# PMSM_500W_Controller_Bridge.net
KiCad netlist of a schematic drawn in Altium Designer
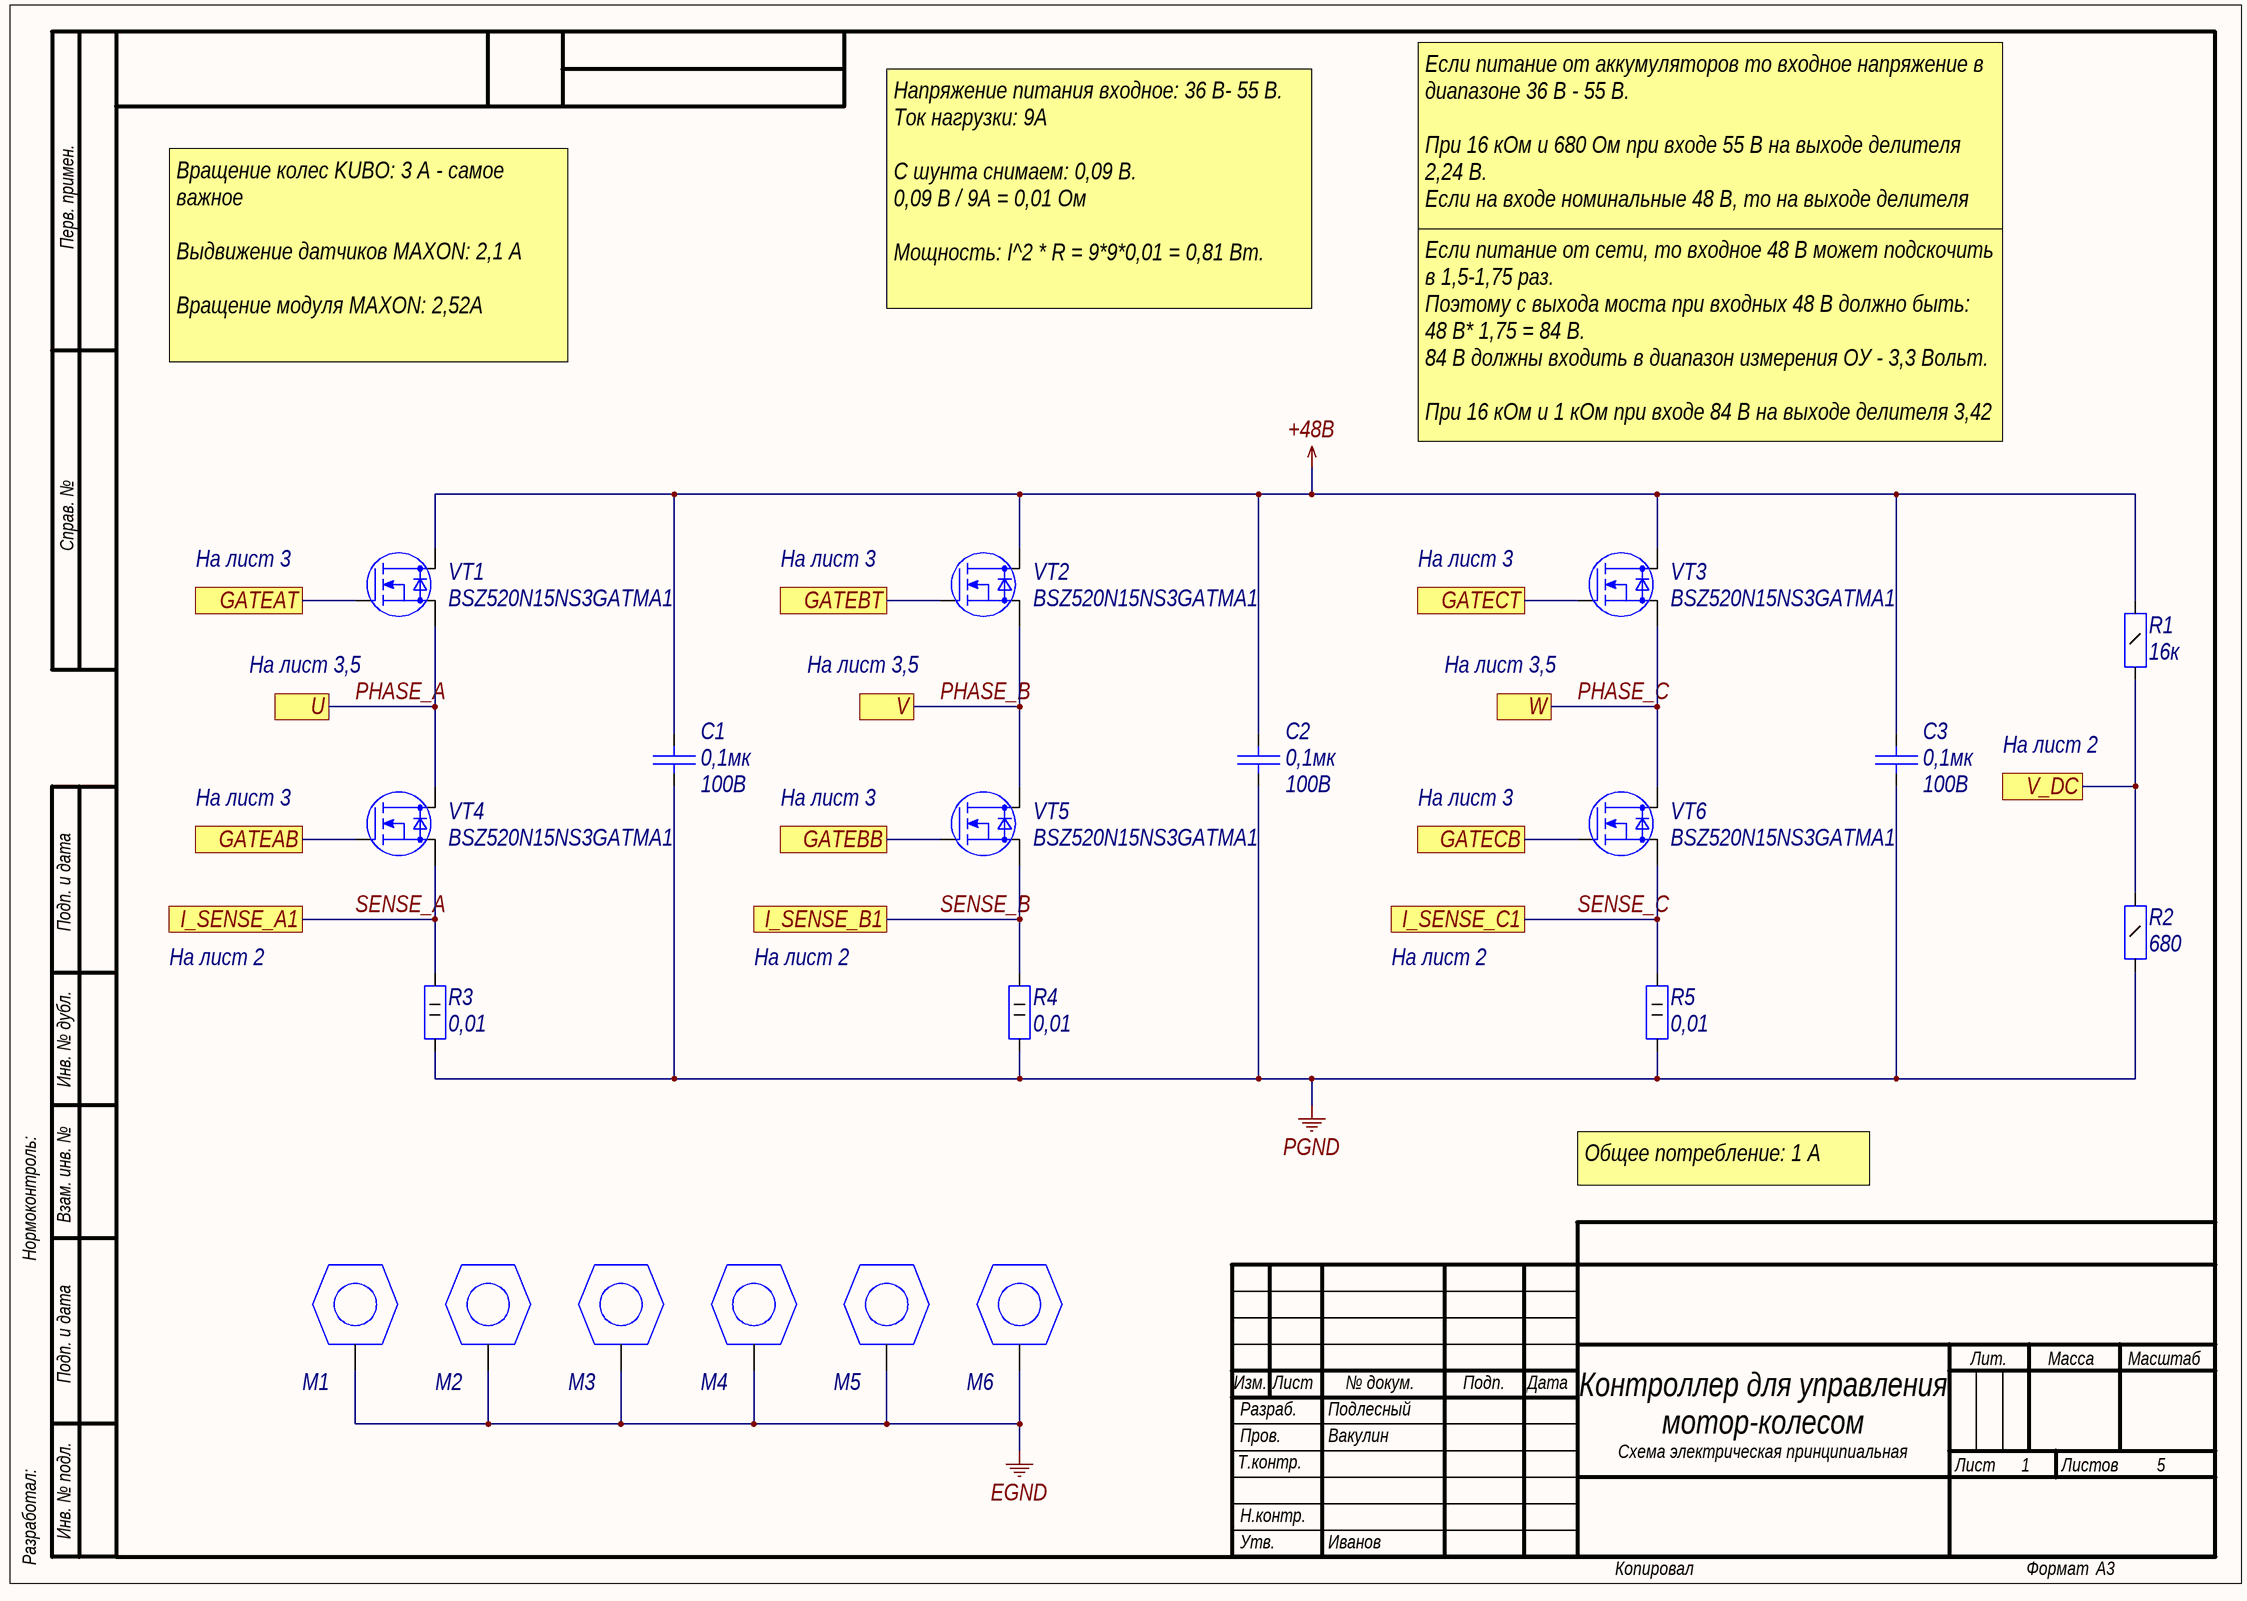
[diagram p0: PMSM_500W_Controller_Bridge.SchDoc]

(export (version "E")
  (design (tool "Eeschema 10.0.6"))
  (components
    (comp (ref "C1")
      (value "0,1мк")
      (footprint "C1206")
      (description "Конденсатор")
      (fields (field (name "VOLTAGE") "100В") (field (name "PART NUMBER") "GRM31C5C2A104JA01L"))
      (libsource (lib "MOP44") (part "Capacitor"))
    )
    (comp (ref "C2")
      (value "0,1мк")
      (footprint "C1206")
      (description "Конденсатор")
      (fields (field (name "VOLTAGE") "100В") (field (name "PART NUMBER") "GRM31C5C2A104JA01L"))
      (libsource (lib "MOP44") (part "Capacitor"))
    )
    (comp (ref "C3")
      (value "0,1мк")
      (footprint "C1206")
      (description "Конденсатор")
      (fields (field (name "VOLTAGE") "100В") (field (name "PART NUMBER") "GRM31C5C2A104JA01L"))
      (libsource (lib "MOP44") (part "Capacitor"))
    )
    (comp (ref "M1") (value "SCREW") (footprint "SCREW3") (libsource (lib "MOP44") (part "SCREW")))
    (comp (ref "M2") (value "SCREW") (footprint "SCREW3") (libsource (lib "MOP44") (part "SCREW")))
    (comp (ref "M3") (value "SCREW") (footprint "SCREW3") (libsource (lib "MOP44") (part "SCREW")))
    (comp (ref "M4") (value "SCREW") (footprint "SCREW3") (libsource (lib "MOP44") (part "SCREW")))
    (comp (ref "M5") (value "SCREW") (footprint "SCREW3") (libsource (lib "MOP44") (part "SCREW")))
    (comp (ref "M6") (value "SCREW") (footprint "SCREW3") (libsource (lib "MOP44") (part "SCREW")))
    (comp (ref "R1")
      (value "16к")
      (footprint "R1206")
      (description "Резистор")
      (fields (field (name "PART NUMBER") "RC1206FR-0716KL") (field (name "POWER") "0,25Вт"))
      (libsource (lib "MOP44") (part "Resistor_0,25Вт"))
    )
    (comp (ref "R2")
      (value "680")
      (footprint "R1206")
      (description "Резистор")
      (fields (field (name "PART NUMBER") "RC1206FR-07680RL") (field (name "POWER") "0,25Вт"))
      (libsource (lib "MOP44") (part "Resistor_0,25Вт"))
    )
    (comp (ref "R3")
      (value "0,01")
      (footprint "R2512")
      (description "Резистор")
      (fields (field (name "PART NUMBER") "CRA2512-FZ-R010ELF") (field (name "POWER") "2Вт"))
      (libsource (lib "MOP44") (part "Resistor_2Вт"))
    )
    (comp (ref "R4")
      (value "0,01")
      (footprint "R2512")
      (description "Резистор")
      (fields (field (name "PART NUMBER") "CRA2512-FZ-R010ELF") (field (name "POWER") "2Вт"))
      (libsource (lib "MOP44") (part "Resistor_2Вт"))
    )
    (comp (ref "R5")
      (value "0,01")
      (footprint "R2512")
      (description "Резистор")
      (fields (field (name "PART NUMBER") "CRA2512-FZ-R010ELF") (field (name "POWER") "2Вт"))
      (libsource (lib "MOP44") (part "Resistor_2Вт"))
    )
    (comp (ref "VT1")
      (value "N-MOSFET")
      (footprint "TSDSON8")
      (fields
        (field (name "PART NUMBER") "BSZ520N15NS3GATMA1")
        (field (name "MANUFACTURER") "Infineon Technologies")
      )
      (libsource (lib "MOP44") (part "N-MOSFET"))
    )
    (comp (ref "VT2")
      (value "N-MOSFET")
      (footprint "TSDSON8")
      (fields
        (field (name "PART NUMBER") "BSZ520N15NS3GATMA1")
        (field (name "MANUFACTURER") "Infineon Technologies")
      )
      (libsource (lib "MOP44") (part "N-MOSFET"))
    )
    (comp (ref "VT3")
      (value "N-MOSFET")
      (footprint "TSDSON8")
      (fields
        (field (name "PART NUMBER") "BSZ520N15NS3GATMA1")
        (field (name "MANUFACTURER") "Infineon Technologies")
      )
      (libsource (lib "MOP44") (part "N-MOSFET"))
    )
    (comp (ref "VT4")
      (value "N-MOSFET")
      (footprint "TSDSON8")
      (fields
        (field (name "PART NUMBER") "BSZ520N15NS3GATMA1")
        (field (name "MANUFACTURER") "Infineon Technologies")
      )
      (libsource (lib "MOP44") (part "N-MOSFET"))
    )
    (comp (ref "VT5")
      (value "N-MOSFET")
      (footprint "TSDSON8")
      (fields
        (field (name "PART NUMBER") "BSZ520N15NS3GATMA1")
        (field (name "MANUFACTURER") "Infineon Technologies")
      )
      (libsource (lib "MOP44") (part "N-MOSFET"))
    )
    (comp (ref "VT6")
      (value "N-MOSFET")
      (footprint "TSDSON8")
      (fields
        (field (name "PART NUMBER") "BSZ520N15NS3GATMA1")
        (field (name "MANUFACTURER") "Infineon Technologies")
      )
      (libsource (lib "MOP44") (part "N-MOSFET"))
    )
  )
  (nets
    (net (code "1") (name "+48B") (class "Default")
      (node (ref "C1") (pin "2") (pinfunction "2_2") (pintype "passive"))
      (node (ref "C2") (pin "2") (pinfunction "2_2") (pintype "passive"))
      (node (ref "C3") (pin "2") (pinfunction "2_2") (pintype "passive"))
      (node (ref "R1") (pin "2") (pinfunction "2_2") (pintype "passive"))
      (node (ref "VT1") (pin "2") (pinfunction "D_2") (pintype "passive"))
      (node (ref "VT2") (pin "2") (pinfunction "D_2") (pintype "passive"))
      (node (ref "VT3") (pin "2") (pinfunction "D_2") (pintype "passive"))
    )
    (net (code "2") (name "/GATEAB") (class "Default")
      (node (ref "VT4") (pin "1") (pinfunction "G_1") (pintype "passive"))
    )
    (net (code "3") (name "/GATEAT") (class "Default")
      (node (ref "VT1") (pin "1") (pinfunction "G_1") (pintype "passive"))
    )
    (net (code "4") (name "/GATEBB") (class "Default")
      (node (ref "VT5") (pin "1") (pinfunction "G_1") (pintype "passive"))
    )
    (net (code "5") (name "/GATEBT") (class "Default")
      (node (ref "VT2") (pin "1") (pinfunction "G_1") (pintype "passive"))
    )
    (net (code "6") (name "/GATECB") (class "Default")
      (node (ref "VT6") (pin "1") (pinfunction "G_1") (pintype "passive"))
    )
    (net (code "7") (name "/GATECT") (class "Default")
      (node (ref "VT3") (pin "1") (pinfunction "G_1") (pintype "passive"))
    )
    (net (code "8") (name "/PHASE_A") (class "Default")
      (node (ref "VT1") (pin "3") (pinfunction "S_3") (pintype "passive"))
      (node (ref "VT4") (pin "2") (pinfunction "D_2") (pintype "passive"))
    )
    (net (code "9") (name "/PHASE_B") (class "Default")
      (node (ref "VT2") (pin "3") (pinfunction "S_3") (pintype "passive"))
      (node (ref "VT5") (pin "2") (pinfunction "D_2") (pintype "passive"))
    )
    (net (code "10") (name "/PHASE_C") (class "Default")
      (node (ref "VT3") (pin "3") (pinfunction "S_3") (pintype "passive"))
      (node (ref "VT6") (pin "2") (pinfunction "D_2") (pintype "passive"))
    )
    (net (code "11") (name "/SENSE_A") (class "Default")
      (node (ref "R3") (pin "2") (pinfunction "5_2") (pintype "passive"))
      (node (ref "VT4") (pin "3") (pinfunction "S_3") (pintype "passive"))
    )
    (net (code "12") (name "/SENSE_B") (class "Default")
      (node (ref "R4") (pin "2") (pinfunction "5_2") (pintype "passive"))
      (node (ref "VT5") (pin "3") (pinfunction "S_3") (pintype "passive"))
    )
    (net (code "13") (name "/SENSE_C") (class "Default")
      (node (ref "R5") (pin "2") (pinfunction "5_2") (pintype "passive"))
      (node (ref "VT6") (pin "3") (pinfunction "S_3") (pintype "passive"))
    )
    (net (code "14") (name "/V_DC") (class "Default")
      (node (ref "R1") (pin "1") (pinfunction "1_1") (pintype "passive"))
      (node (ref "R2") (pin "2") (pinfunction "2_2") (pintype "passive"))
    )
    (net (code "15") (name "EGND") (class "Default")
      (node (ref "M1") (pin "1") (pinfunction "1_1") (pintype "passive"))
      (node (ref "M2") (pin "1") (pinfunction "1_1") (pintype "passive"))
      (node (ref "M3") (pin "1") (pinfunction "1_1") (pintype "passive"))
      (node (ref "M4") (pin "1") (pinfunction "1_1") (pintype "passive"))
      (node (ref "M5") (pin "1") (pinfunction "1_1") (pintype "passive"))
      (node (ref "M6") (pin "1") (pinfunction "1_1") (pintype "passive"))
    )
    (net (code "16") (name "PGND") (class "Default")
      (node (ref "C1") (pin "1") (pinfunction "1_1") (pintype "passive"))
      (node (ref "C2") (pin "1") (pinfunction "1_1") (pintype "passive"))
      (node (ref "C3") (pin "1") (pinfunction "1_1") (pintype "passive"))
      (node (ref "R2") (pin "1") (pinfunction "1_1") (pintype "passive"))
      (node (ref "R3") (pin "1") (pinfunction "1_1") (pintype "passive"))
      (node (ref "R4") (pin "1") (pinfunction "1_1") (pintype "passive"))
      (node (ref "R5") (pin "1") (pinfunction "1_1") (pintype "passive"))
    )
  )
)
